# LDR_RGB.net
KiCad netlist of a schematic drawn in Altium Designer
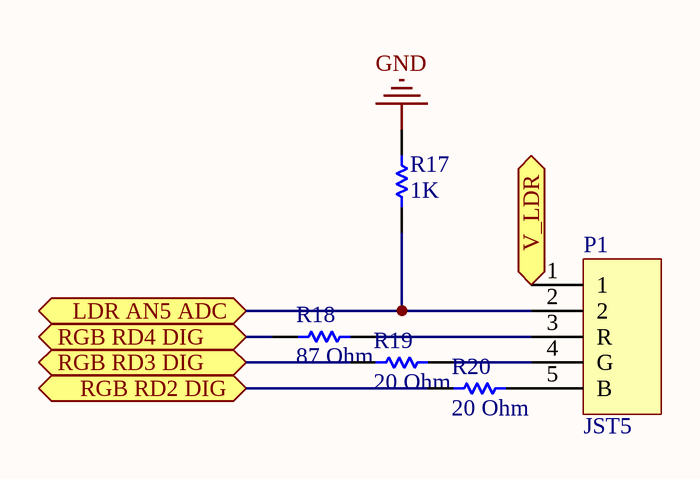
[diagram p0: LDR_RGB.SchDoc]

(export (version "E")
  (design (tool "Eeschema 10.0.6"))
  (components
    (comp (ref "P1")
      (value "JST5")
      (footprint "LDR_RGB")
      (description "Header, 5-Pin")
      (fields (field (name "PUBLISHER") "Altium Limited"))
      (libsource (lib "Miscellaneous Connectors") (part "MHDR1X5"))
    )
    (comp (ref "R17")
      (value "1K")
      (footprint "Resistor0603")
      (description "Resistor")
      (fields (field (name "PUBLISHER") "Altium Limited"))
      (libsource (lib "Miscellaneous Devices") (part "Res1"))
    )
    (comp (ref "R18")
      (value "87 Ohm")
      (footprint "Resistor0603")
      (description "Resistor")
      (fields (field (name "PUBLISHER") "Altium Limited"))
      (libsource (lib "Miscellaneous Devices") (part "Res1"))
    )
    (comp (ref "R19")
      (value "20 Ohm")
      (footprint "Resistor0603")
      (description "Resistor")
      (fields (field (name "PUBLISHER") "Altium Limited"))
      (libsource (lib "Miscellaneous Devices") (part "Res1"))
    )
    (comp (ref "R20")
      (value "20 Ohm")
      (footprint "Resistor0603")
      (description "Resistor")
      (fields (field (name "PUBLISHER") "Altium Limited"))
      (libsource (lib "Miscellaneous Devices") (part "Res1"))
    )
  )
  (nets
    (net (code "1") (name "/LDR AN5 ADC") (class "Default")
      (node (ref "P1") (pin "2") (pinfunction "2_2") (pintype "passive"))
      (node (ref "R17") (pin "1") (pinfunction "1_1") (pintype "passive"))
    )
    (net (code "2") (name "/RGB RD2 DIG") (class "Default")
      (node (ref "R20") (pin "1") (pinfunction "1_1") (pintype "passive"))
    )
    (net (code "3") (name "/RGB RD3 DIG") (class "Default")
      (node (ref "R19") (pin "1") (pinfunction "1_1") (pintype "passive"))
    )
    (net (code "4") (name "/RGB RD4 DIG") (class "Default")
      (node (ref "R18") (pin "1") (pinfunction "1_1") (pintype "passive"))
    )
    (net (code "5") (name "/V_LDR") (class "Default")
      (node (ref "P1") (pin "1") (pinfunction "1_1") (pintype "passive"))
    )
    (net (code "6") (name "GND") (class "Default")
      (node (ref "R17") (pin "2") (pinfunction "2_2") (pintype "passive"))
    )
    (net (code "7") (name "Net-(P1-B)") (class "Default")
      (node (ref "P1") (pin "5") (pinfunction "B_5") (pintype "passive"))
      (node (ref "R20") (pin "2") (pinfunction "2_2") (pintype "passive"))
    )
    (net (code "8") (name "Net-(P1-G)") (class "Default")
      (node (ref "P1") (pin "4") (pinfunction "G_4") (pintype "passive"))
      (node (ref "R19") (pin "2") (pinfunction "2_2") (pintype "passive"))
    )
    (net (code "9") (name "Net-(P1-R)") (class "Default")
      (node (ref "P1") (pin "3") (pinfunction "R_3") (pintype "passive"))
      (node (ref "R18") (pin "2") (pinfunction "2_2") (pintype "passive"))
    )
  )
)
